# Driver.net
KiCad netlist of a schematic drawn in EAGLE
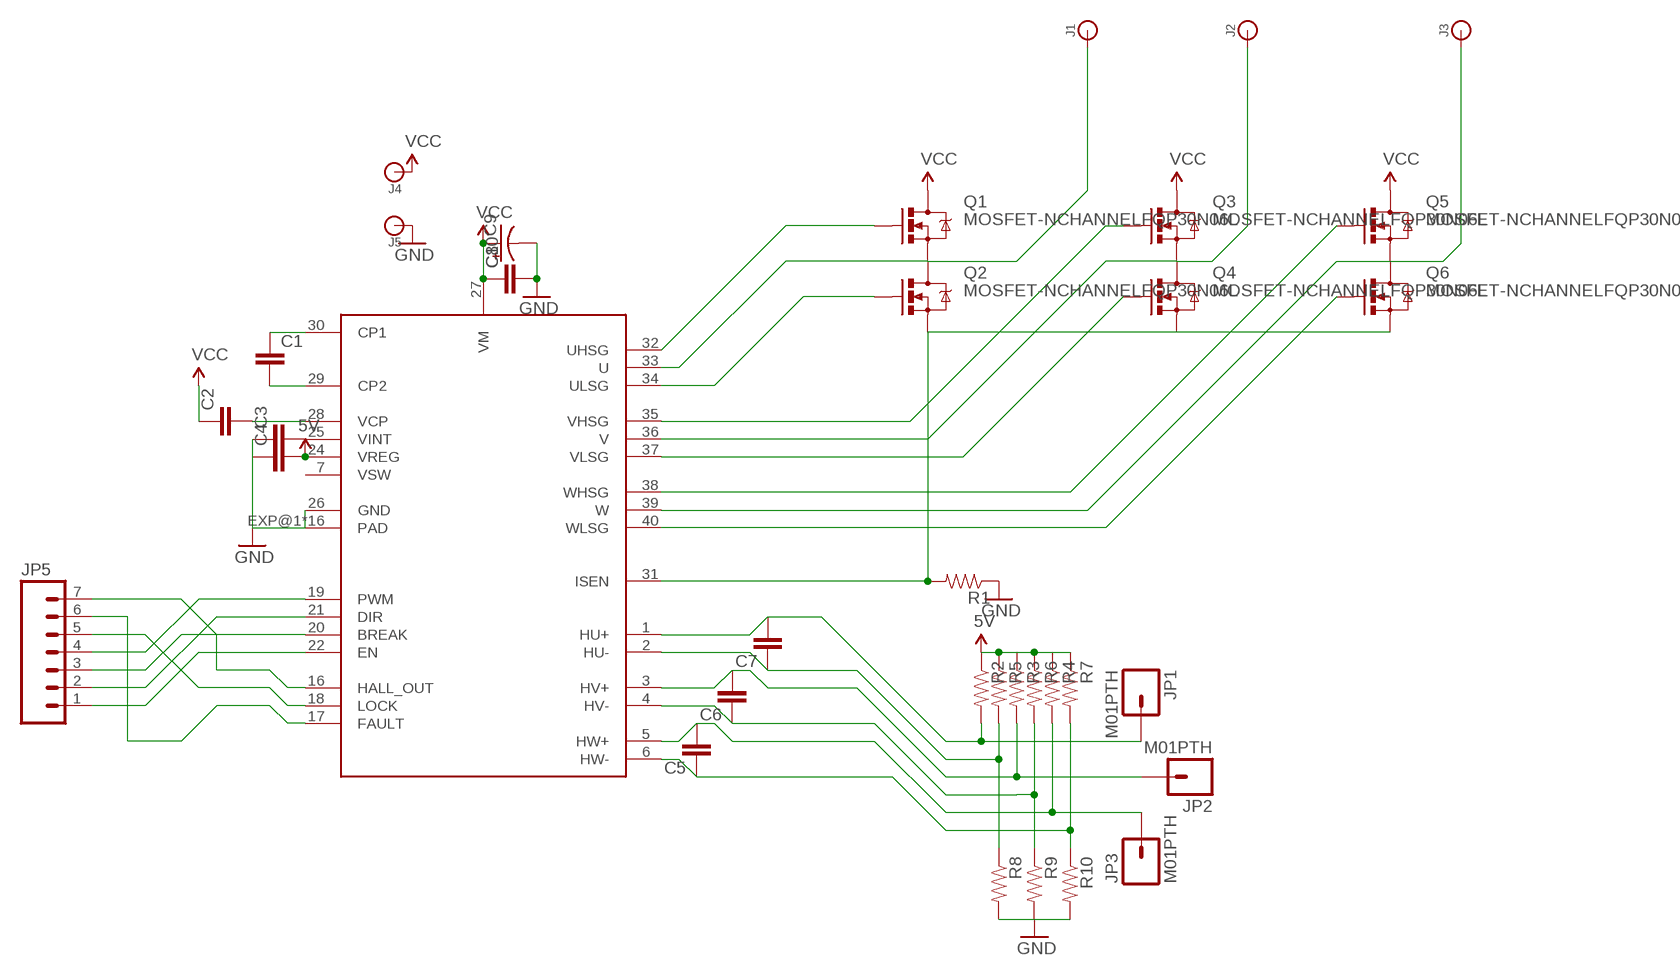
[diagram p0: schematic, sheet 1]

(export (version "E")
  (design (tool "Eeschema 10.0.6"))
  (components
    (comp (ref "C1")
      (value "CAP1206")
      (footprint "eagle-import:1206")
      (libsource (lib "eagle-import") (part "CAP1206"))
    )
    (comp (ref "C2")
      (value "CAP1206")
      (footprint "eagle-import:1206")
      (libsource (lib "eagle-import") (part "CAP1206"))
    )
    (comp (ref "C3")
      (value "CAP1206")
      (footprint "eagle-import:1206")
      (libsource (lib "eagle-import") (part "CAP1206"))
    )
    (comp (ref "C4")
      (value "CAP1206")
      (footprint "eagle-import:1206")
      (libsource (lib "eagle-import") (part "CAP1206"))
    )
    (comp (ref "C5")
      (value "CAP0805")
      (footprint "eagle-import:0805")
      (libsource (lib "eagle-import") (part "CAP0805"))
    )
    (comp (ref "C6")
      (value "CAP0805")
      (footprint "eagle-import:0805")
      (libsource (lib "eagle-import") (part "CAP0805"))
    )
    (comp (ref "C7")
      (value "CAP0805")
      (footprint "eagle-import:0805")
      (libsource (lib "eagle-import") (part "CAP0805"))
    )
    (comp (ref "C8")
      (value "CAP1206")
      (footprint "eagle-import:1206")
      (libsource (lib "eagle-import") (part "CAP1206"))
    )
    (comp (ref "C9")
      (value "CAP_POLPTH4")
      (footprint "eagle-import:CPOL-RADIAL-1000UF-25V")
      (libsource (lib "eagle-import") (part "CAP_POLPTH4"))
    )
    (comp (ref "C10")
      (value "CAP0805")
      (footprint "eagle-import:0805")
      (libsource (lib "eagle-import") (part "CAP0805"))
    )
    (comp (ref "J1")
      (value "BANANA_CONN")
      (footprint "eagle-import:BANANA_CONN")
      (libsource (lib "eagle-import") (part "BANANA_CONN"))
    )
    (comp (ref "J2")
      (value "BANANA_CONN")
      (footprint "eagle-import:BANANA_CONN")
      (libsource (lib "eagle-import") (part "BANANA_CONN"))
    )
    (comp (ref "J3")
      (value "BANANA_CONN")
      (footprint "eagle-import:BANANA_CONN")
      (libsource (lib "eagle-import") (part "BANANA_CONN"))
    )
    (comp (ref "J4")
      (value "BANANA_CONN")
      (footprint "eagle-import:BANANA_CONN")
      (libsource (lib "eagle-import") (part "BANANA_CONN"))
    )
    (comp (ref "J5")
      (value "BANANA_CONN")
      (footprint "eagle-import:BANANA_CONN")
      (libsource (lib "eagle-import") (part "BANANA_CONN"))
    )
    (comp (ref "JP1")
      (value "M01PTH")
      (footprint "eagle-import:1X01")
      (libsource (lib "eagle-import") (part "M01PTH"))
    )
    (comp (ref "JP2")
      (value "M01PTH")
      (footprint "eagle-import:1X01")
      (libsource (lib "eagle-import") (part "M01PTH"))
    )
    (comp (ref "JP3")
      (value "M01PTH")
      (footprint "eagle-import:1X01")
      (libsource (lib "eagle-import") (part "M01PTH"))
    )
    (comp (ref "JP5")
      (value "M07")
      (footprint "eagle-import:1X07")
      (libsource (lib "eagle-import") (part "M07"))
    )
    (comp (ref "Q1")
      (value "MOSFET-NCHANNELFQP30N06L")
      (footprint "eagle-import:TO220V")
      (libsource (lib "eagle-import") (part "MOSFET-NCHANNELFQP30N06L"))
    )
    (comp (ref "Q2")
      (value "MOSFET-NCHANNELFQP30N06L")
      (footprint "eagle-import:TO220V")
      (libsource (lib "eagle-import") (part "MOSFET-NCHANNELFQP30N06L"))
    )
    (comp (ref "Q3")
      (value "MOSFET-NCHANNELFQP30N06L")
      (footprint "eagle-import:TO220V")
      (libsource (lib "eagle-import") (part "MOSFET-NCHANNELFQP30N06L"))
    )
    (comp (ref "Q4")
      (value "MOSFET-NCHANNELFQP30N06L")
      (footprint "eagle-import:TO220V")
      (libsource (lib "eagle-import") (part "MOSFET-NCHANNELFQP30N06L"))
    )
    (comp (ref "Q5")
      (value "MOSFET-NCHANNELFQP30N06L")
      (footprint "eagle-import:TO220V")
      (libsource (lib "eagle-import") (part "MOSFET-NCHANNELFQP30N06L"))
    )
    (comp (ref "Q6")
      (value "MOSFET-NCHANNELFQP30N06L")
      (footprint "eagle-import:TO220V")
      (libsource (lib "eagle-import") (part "MOSFET-NCHANNELFQP30N06L"))
    )
    (comp (ref "R1")
      (value "RESISTOR2010")
      (footprint "eagle-import:R2010")
      (libsource (lib "eagle-import") (part "RESISTOR2010"))
    )
    (comp (ref "R2")
      (value "RESISTOR0805-RES")
      (footprint "eagle-import:0805")
      (libsource (lib "eagle-import") (part "RESISTOR0805-RES"))
    )
    (comp (ref "R3")
      (value "RESISTOR0805-RES")
      (footprint "eagle-import:0805")
      (libsource (lib "eagle-import") (part "RESISTOR0805-RES"))
    )
    (comp (ref "R4")
      (value "RESISTOR0805-RES")
      (footprint "eagle-import:0805")
      (libsource (lib "eagle-import") (part "RESISTOR0805-RES"))
    )
    (comp (ref "R5")
      (value "RESISTOR0805-RES")
      (footprint "eagle-import:0805")
      (libsource (lib "eagle-import") (part "RESISTOR0805-RES"))
    )
    (comp (ref "R6")
      (value "RESISTOR0805-RES")
      (footprint "eagle-import:0805")
      (libsource (lib "eagle-import") (part "RESISTOR0805-RES"))
    )
    (comp (ref "R7")
      (value "RESISTOR0805-RES")
      (footprint "eagle-import:0805")
      (libsource (lib "eagle-import") (part "RESISTOR0805-RES"))
    )
    (comp (ref "R8")
      (value "RESISTOR0805-RES")
      (footprint "eagle-import:0805")
      (libsource (lib "eagle-import") (part "RESISTOR0805-RES"))
    )
    (comp (ref "R9")
      (value "RESISTOR0805-RES")
      (footprint "eagle-import:0805")
      (libsource (lib "eagle-import") (part "RESISTOR0805-RES"))
    )
    (comp (ref "R10")
      (value "RESISTOR0805-RES")
      (footprint "eagle-import:0805")
      (libsource (lib "eagle-import") (part "RESISTOR0805-RES"))
    )
    (comp (ref "U$1")
      (value "DRV8307")
      (footprint "eagle-import:QFN40-6X6")
      (libsource (lib "eagle-import") (part "DRV8307"))
    )
  )
  (nets
    (net (code "1") (name "5V") (class "Default")
      (node (ref "C4") (pin "2") (pinfunction "2_2") (pintype "passive"))
      (node (ref "R2") (pin "1") (pinfunction "1_1") (pintype "passive"))
      (node (ref "R3") (pin "1") (pinfunction "1_1") (pintype "passive"))
      (node (ref "R4") (pin "1") (pinfunction "1_1") (pintype "passive"))
      (node (ref "R5") (pin "1") (pinfunction "1_1") (pintype "passive"))
      (node (ref "R6") (pin "1") (pinfunction "1_1") (pintype "passive"))
      (node (ref "R7") (pin "1") (pinfunction "1_1") (pintype "passive"))
      (node (ref "U$1") (pin "24") (pinfunction "VREG_24") (pintype "bidirectional"))
    )
    (net (code "2") (name "GND") (class "Default")
      (node (ref "C10") (pin "2") (pinfunction "2_2") (pintype "passive"))
      (node (ref "C3") (pin "1") (pinfunction "1_1") (pintype "passive"))
      (node (ref "C4") (pin "1") (pinfunction "1_1") (pintype "passive"))
      (node (ref "C8") (pin "2") (pinfunction "2_2") (pintype "passive"))
      (node (ref "C9") (pin "-") (pinfunction "-_-") (pintype "passive"))
      (node (ref "J5") (pin "P$1") (pinfunction "1_P$1") (pintype "passive"))
      (node (ref "R1") (pin "1") (pinfunction "1_1") (pintype "passive"))
      (node (ref "R10") (pin "2") (pinfunction "2_2") (pintype "passive"))
      (node (ref "R8") (pin "2") (pinfunction "2_2") (pintype "passive"))
      (node (ref "R9") (pin "2") (pinfunction "2_2") (pintype "passive"))
      (node (ref "U$1") (pin "26") (pinfunction "GND_26") (pintype "bidirectional"))
      (node (ref "U$1") (pin "EXP@1") (pinfunction "PAD_EXP@1") (pintype "bidirectional"))
      (node (ref "U$1") (pin "EXP@10") (pinfunction "PAD_EXP@10") (pintype "bidirectional"))
      (node (ref "U$1") (pin "EXP@11") (pinfunction "PAD_EXP@11") (pintype "bidirectional"))
      (node (ref "U$1") (pin "EXP@12") (pinfunction "PAD_EXP@12") (pintype "bidirectional"))
      (node (ref "U$1") (pin "EXP@13") (pinfunction "PAD_EXP@13") (pintype "bidirectional"))
      (node (ref "U$1") (pin "EXP@14") (pinfunction "PAD_EXP@14") (pintype "bidirectional"))
      (node (ref "U$1") (pin "EXP@15") (pinfunction "PAD_EXP@15") (pintype "bidirectional"))
      (node (ref "U$1") (pin "EXP@16") (pinfunction "PAD_EXP@16") (pintype "bidirectional"))
      (node (ref "U$1") (pin "EXP@2") (pinfunction "PAD_EXP@2") (pintype "bidirectional"))
      (node (ref "U$1") (pin "EXP@3") (pinfunction "PAD_EXP@3") (pintype "bidirectional"))
      (node (ref "U$1") (pin "EXP@4") (pinfunction "PAD_EXP@4") (pintype "bidirectional"))
      (node (ref "U$1") (pin "EXP@5") (pinfunction "PAD_EXP@5") (pintype "bidirectional"))
      (node (ref "U$1") (pin "EXP@6") (pinfunction "PAD_EXP@6") (pintype "bidirectional"))
      (node (ref "U$1") (pin "EXP@7") (pinfunction "PAD_EXP@7") (pintype "bidirectional"))
      (node (ref "U$1") (pin "EXP@8") (pinfunction "PAD_EXP@8") (pintype "bidirectional"))
      (node (ref "U$1") (pin "EXP@9") (pinfunction "PAD_EXP@9") (pintype "bidirectional"))
    )
    (net (code "3") (name "Net-(J1-1)") (class "Default")
      (node (ref "J1") (pin "P$1") (pinfunction "1_P$1") (pintype "passive"))
      (node (ref "Q1") (pin "3") (pinfunction "S_3") (pintype "passive"))
      (node (ref "Q2") (pin "2") (pinfunction "D_2") (pintype "passive"))
      (node (ref "U$1") (pin "33") (pinfunction "U_33") (pintype "bidirectional"))
    )
    (net (code "4") (name "Net-(J2-1)") (class "Default")
      (node (ref "J2") (pin "P$1") (pinfunction "1_P$1") (pintype "passive"))
      (node (ref "Q3") (pin "3") (pinfunction "S_3") (pintype "passive"))
      (node (ref "Q4") (pin "2") (pinfunction "D_2") (pintype "passive"))
      (node (ref "U$1") (pin "36") (pinfunction "V_36") (pintype "bidirectional"))
    )
    (net (code "5") (name "Net-(J3-1)") (class "Default")
      (node (ref "J3") (pin "P$1") (pinfunction "1_P$1") (pintype "passive"))
      (node (ref "Q5") (pin "3") (pinfunction "S_3") (pintype "passive"))
      (node (ref "Q6") (pin "2") (pinfunction "D_2") (pintype "passive"))
      (node (ref "U$1") (pin "39") (pinfunction "W_39") (pintype "bidirectional"))
    )
    (net (code "6") (name "Net-(Q1-G)") (class "Default")
      (node (ref "Q1") (pin "1") (pinfunction "G_1") (pintype "passive"))
      (node (ref "U$1") (pin "32") (pinfunction "UHSG_32") (pintype "bidirectional"))
    )
    (net (code "7") (name "Net-(Q2-G)") (class "Default")
      (node (ref "Q2") (pin "1") (pinfunction "G_1") (pintype "passive"))
      (node (ref "U$1") (pin "34") (pinfunction "ULSG_34") (pintype "bidirectional"))
    )
    (net (code "8") (name "Net-(Q2-S)") (class "Default")
      (node (ref "Q2") (pin "3") (pinfunction "S_3") (pintype "passive"))
      (node (ref "Q4") (pin "3") (pinfunction "S_3") (pintype "passive"))
      (node (ref "Q6") (pin "3") (pinfunction "S_3") (pintype "passive"))
      (node (ref "R1") (pin "2") (pinfunction "2_2") (pintype "passive"))
      (node (ref "U$1") (pin "31") (pinfunction "ISEN_31") (pintype "bidirectional"))
    )
    (net (code "9") (name "Net-(Q3-G)") (class "Default")
      (node (ref "Q3") (pin "1") (pinfunction "G_1") (pintype "passive"))
      (node (ref "U$1") (pin "35") (pinfunction "VHSG_35") (pintype "bidirectional"))
    )
    (net (code "10") (name "Net-(Q4-G)") (class "Default")
      (node (ref "Q4") (pin "1") (pinfunction "G_1") (pintype "passive"))
      (node (ref "U$1") (pin "37") (pinfunction "VLSG_37") (pintype "bidirectional"))
    )
    (net (code "11") (name "Net-(Q5-G)") (class "Default")
      (node (ref "Q5") (pin "1") (pinfunction "G_1") (pintype "passive"))
      (node (ref "U$1") (pin "38") (pinfunction "WHSG_38") (pintype "bidirectional"))
    )
    (net (code "12") (name "Net-(Q6-G)") (class "Default")
      (node (ref "Q6") (pin "1") (pinfunction "G_1") (pintype "passive"))
      (node (ref "U$1") (pin "40") (pinfunction "WLSG_40") (pintype "bidirectional"))
    )
    (net (code "13") (name "Net-(U$1-BREAK)") (class "Default")
      (node (ref "JP5") (pin "3") (pinfunction "3_3") (pintype "passive"))
      (node (ref "U$1") (pin "20") (pinfunction "BREAK_20") (pintype "bidirectional"))
    )
    (net (code "14") (name "Net-(U$1-CP1)") (class "Default")
      (node (ref "C1") (pin "1") (pinfunction "1_1") (pintype "passive"))
      (node (ref "U$1") (pin "30") (pinfunction "CP1_30") (pintype "bidirectional"))
    )
    (net (code "15") (name "Net-(U$1-CP2)") (class "Default")
      (node (ref "C1") (pin "2") (pinfunction "2_2") (pintype "passive"))
      (node (ref "U$1") (pin "29") (pinfunction "CP2_29") (pintype "bidirectional"))
    )
    (net (code "16") (name "Net-(U$1-DIR)") (class "Default")
      (node (ref "JP5") (pin "2") (pinfunction "2_2") (pintype "passive"))
      (node (ref "U$1") (pin "21") (pinfunction "DIR_21") (pintype "bidirectional"))
    )
    (net (code "17") (name "Net-(U$1-EN)") (class "Default")
      (node (ref "JP5") (pin "1") (pinfunction "1_1") (pintype "passive"))
      (node (ref "U$1") (pin "22") (pinfunction "EN_22") (pintype "bidirectional"))
    )
    (net (code "18") (name "Net-(U$1-FAULT)") (class "Default")
      (node (ref "JP5") (pin "6") (pinfunction "6_6") (pintype "passive"))
      (node (ref "U$1") (pin "17") (pinfunction "FAULT_17") (pintype "bidirectional"))
    )
    (net (code "19") (name "Net-(U$1-HALL_OUT)") (class "Default")
      (node (ref "JP5") (pin "7") (pinfunction "7_7") (pintype "passive"))
      (node (ref "U$1") (pin "16") (pinfunction "HALL_OUT_16") (pintype "bidirectional"))
    )
    (net (code "20") (name "Net-(U$1-HU+)") (class "Default")
      (node (ref "C7") (pin "2") (pinfunction "2_2") (pintype "passive"))
      (node (ref "JP1") (pin "1") (pinfunction "1_1") (pintype "passive"))
      (node (ref "R2") (pin "2") (pinfunction "2_2") (pintype "passive"))
      (node (ref "U$1") (pin "1") (pinfunction "HU+_1") (pintype "bidirectional"))
    )
    (net (code "21") (name "Net-(U$1-HU-)") (class "Default")
      (node (ref "C7") (pin "1") (pinfunction "1_1") (pintype "passive"))
      (node (ref "R5") (pin "2") (pinfunction "2_2") (pintype "passive"))
      (node (ref "R8") (pin "1") (pinfunction "1_1") (pintype "passive"))
      (node (ref "U$1") (pin "2") (pinfunction "HU-_2") (pintype "bidirectional"))
    )
    (net (code "22") (name "Net-(U$1-HV+)") (class "Default")
      (node (ref "C6") (pin "2") (pinfunction "2_2") (pintype "passive"))
      (node (ref "JP2") (pin "1") (pinfunction "1_1") (pintype "passive"))
      (node (ref "R3") (pin "2") (pinfunction "2_2") (pintype "passive"))
      (node (ref "U$1") (pin "3") (pinfunction "HV+_3") (pintype "bidirectional"))
    )
    (net (code "23") (name "Net-(U$1-HV-)") (class "Default")
      (node (ref "C6") (pin "1") (pinfunction "1_1") (pintype "passive"))
      (node (ref "R6") (pin "2") (pinfunction "2_2") (pintype "passive"))
      (node (ref "R9") (pin "1") (pinfunction "1_1") (pintype "passive"))
      (node (ref "U$1") (pin "4") (pinfunction "HV-_4") (pintype "bidirectional"))
    )
    (net (code "24") (name "Net-(U$1-HW+)") (class "Default")
      (node (ref "C5") (pin "2") (pinfunction "2_2") (pintype "passive"))
      (node (ref "JP3") (pin "1") (pinfunction "1_1") (pintype "passive"))
      (node (ref "R4") (pin "2") (pinfunction "2_2") (pintype "passive"))
      (node (ref "U$1") (pin "5") (pinfunction "HW+_5") (pintype "bidirectional"))
    )
    (net (code "25") (name "Net-(U$1-HW-)") (class "Default")
      (node (ref "C5") (pin "1") (pinfunction "1_1") (pintype "passive"))
      (node (ref "R10") (pin "1") (pinfunction "1_1") (pintype "passive"))
      (node (ref "R7") (pin "2") (pinfunction "2_2") (pintype "passive"))
      (node (ref "U$1") (pin "6") (pinfunction "HW-_6") (pintype "bidirectional"))
    )
    (net (code "26") (name "Net-(U$1-LOCK)") (class "Default")
      (node (ref "JP5") (pin "5") (pinfunction "5_5") (pintype "passive"))
      (node (ref "U$1") (pin "18") (pinfunction "LOCK_18") (pintype "bidirectional"))
    )
    (net (code "27") (name "Net-(U$1-PWM)") (class "Default")
      (node (ref "JP5") (pin "4") (pinfunction "4_4") (pintype "passive"))
      (node (ref "U$1") (pin "19") (pinfunction "PWM_19") (pintype "bidirectional"))
    )
    (net (code "28") (name "Net-(U$1-VCP)") (class "Default")
      (node (ref "C2") (pin "2") (pinfunction "2_2") (pintype "passive"))
      (node (ref "U$1") (pin "28") (pinfunction "VCP_28") (pintype "bidirectional"))
    )
    (net (code "29") (name "Net-(U$1-VINT)") (class "Default")
      (node (ref "C3") (pin "2") (pinfunction "2_2") (pintype "passive"))
      (node (ref "U$1") (pin "25") (pinfunction "VINT_25") (pintype "bidirectional"))
    )
    (net (code "30") (name "VCC") (class "Default")
      (node (ref "C10") (pin "1") (pinfunction "1_1") (pintype "passive"))
      (node (ref "C2") (pin "1") (pinfunction "1_1") (pintype "passive"))
      (node (ref "C8") (pin "1") (pinfunction "1_1") (pintype "passive"))
      (node (ref "C9") (pin "+") (pinfunction "+_+") (pintype "passive"))
      (node (ref "J4") (pin "P$1") (pinfunction "1_P$1") (pintype "passive"))
      (node (ref "Q1") (pin "2") (pinfunction "D_2") (pintype "passive"))
      (node (ref "Q3") (pin "2") (pinfunction "D_2") (pintype "passive"))
      (node (ref "Q5") (pin "2") (pinfunction "D_2") (pintype "passive"))
      (node (ref "U$1") (pin "27") (pinfunction "VM_27") (pintype "bidirectional"))
    )
    (net (code "31") (name "unconnected-(U$1-VSW-Pad7)") (class "Default")
      (node (ref "U$1") (pin "7") (pinfunction "VSW_7") (pintype "bidirectional"))
    )
  )
)
